# PDM.net
KiCad netlist of a schematic drawn in Altium Designer
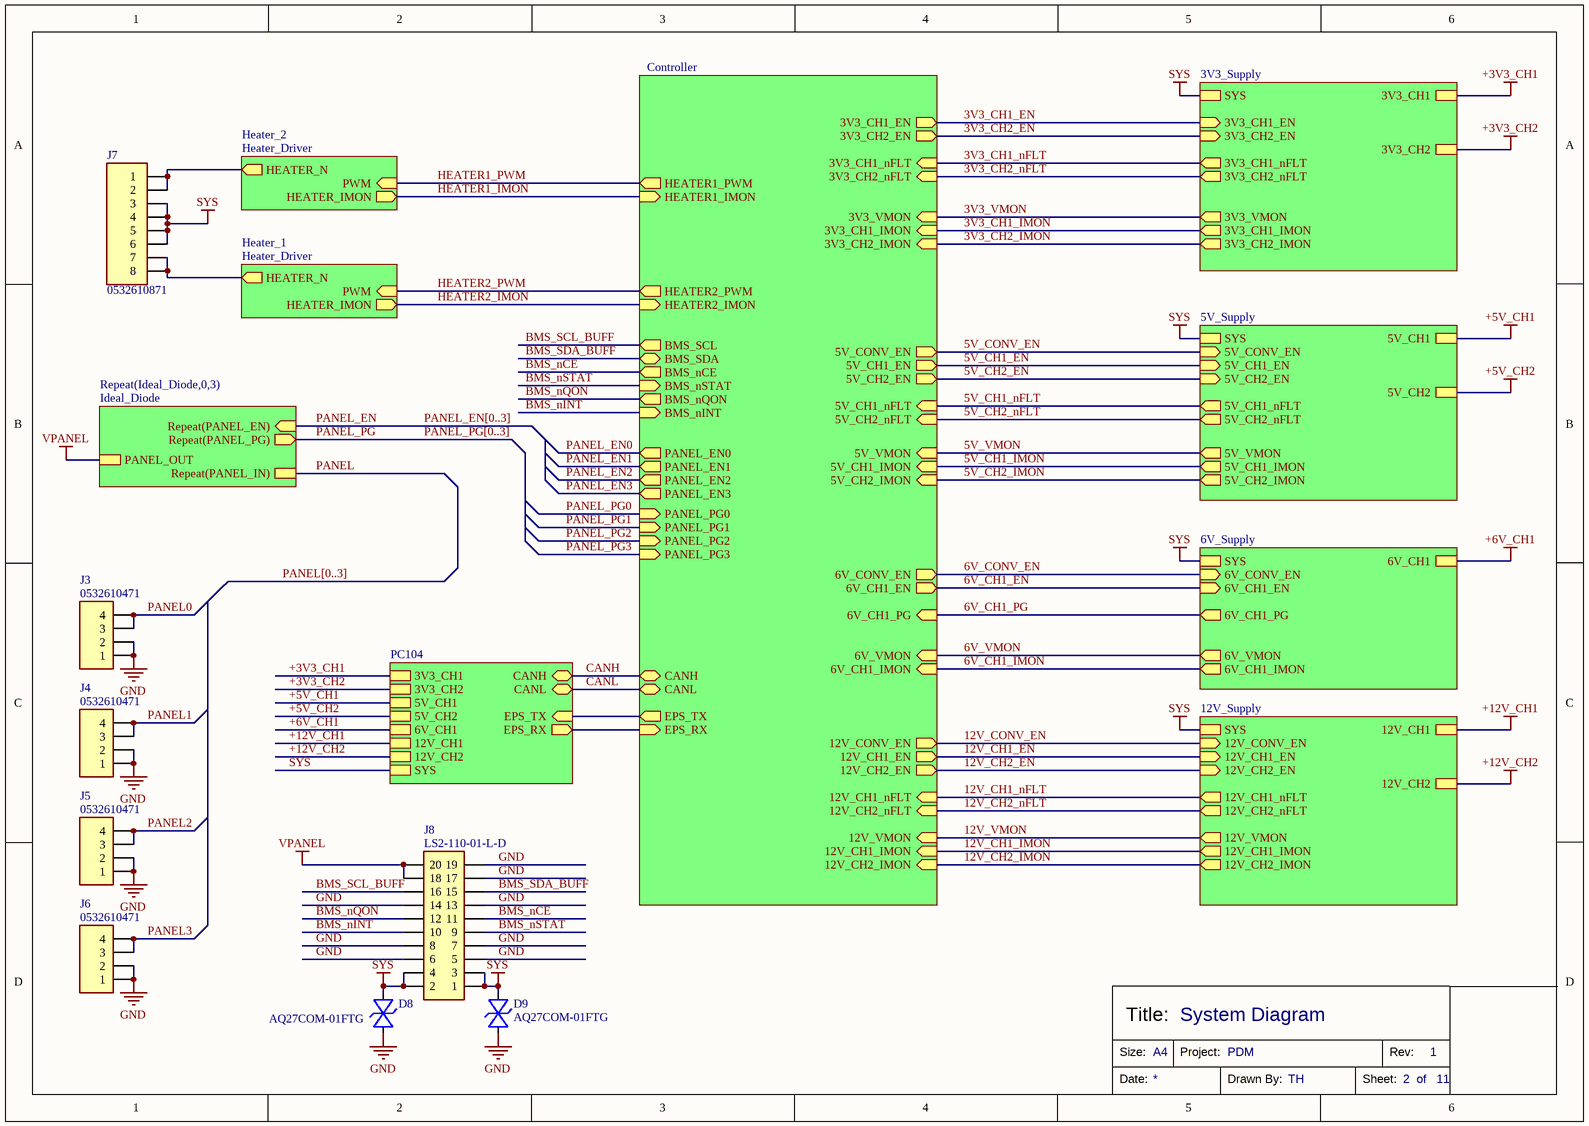
[diagram p0: PDM.SchDoc]

(export (version "E")
  (design (tool "Eeschema 10.0.6"))
  (components
    (comp (ref "D8")
      (value "AQ27COM-01FTG")
      (footprint "SOD-323")
      (description "Transient Voltage Suppression Diodes - TVS 27V 4A 30kV 12pF SOD323 Diode Array")
      (fields
        (field (name "PART NUMBER") "AQ27COM-01FTG")
        (field (name "DISTRIBUTOR PART NUMBER") "18-AQ27COM-01FTGCT-ND")
      )
      (libsource (lib "Ahristi_Library") (part "AQ27COM-01FTG"))
    )
    (comp (ref "D9")
      (value "AQ27COM-01FTG")
      (footprint "SOD-323")
      (description "Transient Voltage Suppression Diodes - TVS 27V 4A 30kV 12pF SOD323 Diode Array")
      (fields
        (field (name "PART NUMBER") "AQ27COM-01FTG")
        (field (name "DISTRIBUTOR PART NUMBER") "18-AQ27COM-01FTGCT-ND")
      )
      (libsource (lib "Ahristi_Library") (part "AQ27COM-01FTG"))
    )
    (comp (ref "J3")
      (value "0532610471")
      (footprint "0532610471")
      (description "Connector Header Surface Mount, Right Angle 4 position 0.049\" (1.25mm) Molex Picoblade")
      (fields (field (name "DISTRIBUTOR PART NUMBER") "WM7622CT-ND"))
      (libsource (lib "Ahristi_Library") (part "0532610471"))
    )
    (comp (ref "J4")
      (value "0532610471")
      (footprint "0532610471")
      (description "Connector Header Surface Mount, Right Angle 4 position 0.049\" (1.25mm) Molex Picoblade")
      (fields (field (name "DISTRIBUTOR PART NUMBER") "WM7622CT-ND"))
      (libsource (lib "Ahristi_Library") (part "0532610471"))
    )
    (comp (ref "J5")
      (value "0532610471")
      (footprint "0532610471")
      (description "Connector Header Surface Mount, Right Angle 4 position 0.049\" (1.25mm) Molex Picoblade")
      (fields (field (name "DISTRIBUTOR PART NUMBER") "WM7622CT-ND"))
      (libsource (lib "Ahristi_Library") (part "0532610471"))
    )
    (comp (ref "J6")
      (value "0532610471")
      (footprint "0532610471")
      (description "Connector Header Surface Mount, Right Angle 4 position 0.049\" (1.25mm) Molex Picoblade")
      (fields (field (name "DISTRIBUTOR PART NUMBER") "WM7622CT-ND"))
      (libsource (lib "Ahristi_Library") (part "0532610471"))
    )
    (comp (ref "J7")
      (value "0532610871")
      (footprint "0532610871")
      (description "Connector Header Surface Mount, Right Angle 8 position 0.049\" (1.25mm) Picoblade")
      (fields (field (name "DISTRIBUTOR PART NUMBER") "WM7624CT-ND"))
      (libsource (lib "Ahristi_Library") (part "0532610871"))
    )
    (comp (ref "J8")
      (value "LS2-110-01-L-D")
      (footprint "LS2-110-01-L-D")
      (description "Connector Self Mating 20 Position , Non-Gendered, Hermaphroditic Through Hole Gold")
      (fields (field (name "DISTRIBUTOR PART NUMBER") "SAM9665-ND"))
      (libsource (lib "Ahristi_Library") (part "LS2-110-01-L-D"))
    )
  )
  (nets
    (net (code "36") (name "/BMS_SCL_BUFF") (class "Default")
      (node (ref "J8") (pin "16") (pinfunction "16_16") (pintype "passive"))
    )
    (net (code "37") (name "/BMS_SDA_BUFF") (class "Default")
      (node (ref "J8") (pin "15") (pinfunction "15_15") (pintype "passive"))
    )
    (net (code "38") (name "/BMS_nCE") (class "Default")
      (node (ref "J8") (pin "11") (pinfunction "11_11") (pintype "passive"))
    )
    (net (code "39") (name "/BMS_nINT") (class "Default")
      (node (ref "J8") (pin "10") (pinfunction "10_10") (pintype "passive"))
    )
    (net (code "40") (name "/BMS_nQON") (class "Default")
      (node (ref "J8") (pin "12") (pinfunction "12_12") (pintype "passive"))
    )
    (net (code "41") (name "/BMS_nSTAT") (class "Default")
      (node (ref "J8") (pin "9") (pinfunction "9_9") (pintype "passive"))
    )
    (net (code "50") (name "/HEATER_N") (class "Default")
      (node (ref "J7") (pin "1") (pinfunction "1_1") (pintype "passive"))
      (node (ref "J7") (pin "2") (pinfunction "2_2") (pintype "passive"))
    )
    (net (code "51") (name "/HEATER_N_1") (class "Default")
      (node (ref "J7") (pin "7") (pinfunction "7_7") (pintype "passive"))
      (node (ref "J7") (pin "8") (pinfunction "8_8") (pintype "passive"))
    )
    (net (code "53") (name "/PANEL0") (class "Default")
      (node (ref "J3") (pin "3") (pinfunction "3_3") (pintype "passive"))
      (node (ref "J3") (pin "4") (pinfunction "4_4") (pintype "passive"))
    )
    (net (code "54") (name "/PANEL1") (class "Default")
      (node (ref "J4") (pin "3") (pinfunction "3_3") (pintype "passive"))
      (node (ref "J4") (pin "4") (pinfunction "4_4") (pintype "passive"))
    )
    (net (code "55") (name "/PANEL2") (class "Default")
      (node (ref "J5") (pin "3") (pinfunction "3_3") (pintype "passive"))
      (node (ref "J5") (pin "4") (pinfunction "4_4") (pintype "passive"))
    )
    (net (code "56") (name "/PANEL3") (class "Default")
      (node (ref "J6") (pin "3") (pinfunction "3_3") (pintype "passive"))
      (node (ref "J6") (pin "4") (pinfunction "4_4") (pintype "passive"))
    )
    (net (code "70") (name "GND") (class "Default")
      (node (ref "D8") (pin "A") (pinfunction "A_A") (pintype "passive"))
      (node (ref "D9") (pin "A") (pinfunction "A_A") (pintype "passive"))
      (node (ref "J3") (pin "1") (pinfunction "1_1") (pintype "passive"))
      (node (ref "J3") (pin "2") (pinfunction "2_2") (pintype "passive"))
      (node (ref "J4") (pin "1") (pinfunction "1_1") (pintype "passive"))
      (node (ref "J4") (pin "2") (pinfunction "2_2") (pintype "passive"))
      (node (ref "J5") (pin "1") (pinfunction "1_1") (pintype "passive"))
      (node (ref "J5") (pin "2") (pinfunction "2_2") (pintype "passive"))
      (node (ref "J6") (pin "1") (pinfunction "1_1") (pintype "passive"))
      (node (ref "J6") (pin "2") (pinfunction "2_2") (pintype "passive"))
      (node (ref "J8") (pin "13") (pinfunction "13_13") (pintype "passive"))
      (node (ref "J8") (pin "14") (pinfunction "14_14") (pintype "passive"))
      (node (ref "J8") (pin "17") (pinfunction "17_17") (pintype "passive"))
      (node (ref "J8") (pin "19") (pinfunction "19_19") (pintype "passive"))
      (node (ref "J8") (pin "5") (pinfunction "5_5") (pintype "passive"))
      (node (ref "J8") (pin "6") (pinfunction "6_6") (pintype "passive"))
      (node (ref "J8") (pin "7") (pinfunction "7_7") (pintype "passive"))
      (node (ref "J8") (pin "8") (pinfunction "8_8") (pintype "passive"))
    )
    (net (code "71") (name "SYS") (class "Default")
      (node (ref "D8") (pin "K") (pinfunction "K_K") (pintype "passive"))
      (node (ref "D9") (pin "K") (pinfunction "K_K") (pintype "passive"))
      (node (ref "J7") (pin "3") (pinfunction "3_3") (pintype "passive"))
      (node (ref "J7") (pin "4") (pinfunction "4_4") (pintype "passive"))
      (node (ref "J7") (pin "5") (pinfunction "5_5") (pintype "passive"))
      (node (ref "J7") (pin "6") (pinfunction "6_6") (pintype "passive"))
      (node (ref "J8") (pin "1") (pinfunction "1_1") (pintype "passive"))
      (node (ref "J8") (pin "2") (pinfunction "2_2") (pintype "passive"))
      (node (ref "J8") (pin "3") (pinfunction "3_3") (pintype "passive"))
      (node (ref "J8") (pin "4") (pinfunction "4_4") (pintype "passive"))
    )
    (net (code "72") (name "VPANEL") (class "Default")
      (node (ref "J8") (pin "18") (pinfunction "18_18") (pintype "passive"))
      (node (ref "J8") (pin "20") (pinfunction "20_20") (pintype "passive"))
    )
  )
)
